# Audio-Board.net
KiCad netlist of a schematic drawn in EAGLE
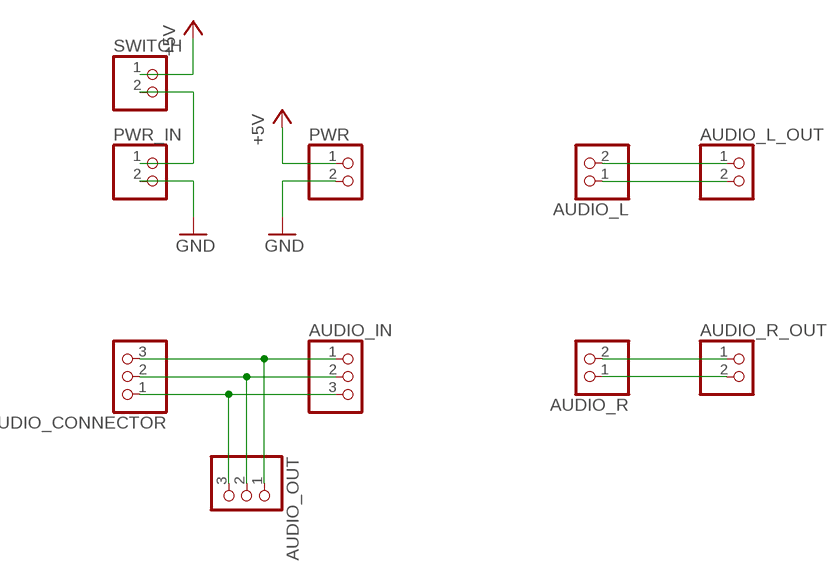
[diagram p0: schematic, sheet 1]

(export (version "E")
  (design (tool "Eeschema 10.0.6"))
  (components
    (comp (ref "AUDIO_CONNECTOR")
      (value "PINHD-1X3")
      (footprint "eagle-import:1X03")
      (libsource (lib "eagle-import") (part "PINHD-1X3"))
    )
    (comp (ref "AUDIO_IN")
      (value "PINHD-1X3")
      (footprint "eagle-import:1X03")
      (libsource (lib "eagle-import") (part "PINHD-1X3"))
    )
    (comp (ref "AUDIO_L")
      (value "PINHD-1X2")
      (footprint "eagle-import:1X02")
      (libsource (lib "eagle-import") (part "PINHD-1X2"))
    )
    (comp (ref "AUDIO_L_OUT")
      (value "PINHD-1X2/90")
      (footprint "eagle-import:1X02_90")
      (libsource (lib "eagle-import") (part "PINHD-1X2/90"))
    )
    (comp (ref "AUDIO_OUT")
      (value "PINHD-1X3")
      (footprint "eagle-import:1X03")
      (libsource (lib "eagle-import") (part "PINHD-1X3"))
    )
    (comp (ref "AUDIO_R")
      (value "PINHD-1X2")
      (footprint "eagle-import:1X02")
      (libsource (lib "eagle-import") (part "PINHD-1X2"))
    )
    (comp (ref "AUDIO_R_OUT")
      (value "PINHD-1X2/90")
      (footprint "eagle-import:1X02_90")
      (libsource (lib "eagle-import") (part "PINHD-1X2/90"))
    )
    (comp (ref "PWR")
      (value "PINHD-1X2")
      (footprint "eagle-import:1X02")
      (libsource (lib "eagle-import") (part "PINHD-1X2"))
    )
    (comp (ref "PWR_IN")
      (value "PINHD-1X2/90")
      (footprint "eagle-import:1X02_90")
      (libsource (lib "eagle-import") (part "PINHD-1X2/90"))
    )
    (comp (ref "SWITCH")
      (value "PINHD-1X2")
      (footprint "eagle-import:1X02")
      (libsource (lib "eagle-import") (part "PINHD-1X2"))
    )
  )
  (nets
    (net (code "1") (name "+5V") (class "Default")
      (node (ref "PWR") (pin "1") (pinfunction "1_1") (pintype "passive"))
      (node (ref "SWITCH") (pin "1") (pinfunction "1_1") (pintype "passive"))
    )
    (net (code "2") (name "GND") (class "Default")
      (node (ref "PWR") (pin "2") (pinfunction "2_2") (pintype "passive"))
      (node (ref "PWR_IN") (pin "2") (pinfunction "2_2") (pintype "passive"))
    )
    (net (code "3") (name "Net-(AUDIO_CONNECTOR-Pad1)") (class "Default")
      (node (ref "AUDIO_CONNECTOR") (pin "1") (pinfunction "1_1") (pintype "passive"))
      (node (ref "AUDIO_IN") (pin "3") (pinfunction "3_3") (pintype "passive"))
      (node (ref "AUDIO_OUT") (pin "3") (pinfunction "3_3") (pintype "passive"))
    )
    (net (code "4") (name "Net-(AUDIO_CONNECTOR-Pad2)") (class "Default")
      (node (ref "AUDIO_CONNECTOR") (pin "2") (pinfunction "2_2") (pintype "passive"))
      (node (ref "AUDIO_IN") (pin "2") (pinfunction "2_2") (pintype "passive"))
      (node (ref "AUDIO_OUT") (pin "2") (pinfunction "2_2") (pintype "passive"))
    )
    (net (code "5") (name "Net-(AUDIO_CONNECTOR-Pad3)") (class "Default")
      (node (ref "AUDIO_CONNECTOR") (pin "3") (pinfunction "3_3") (pintype "passive"))
      (node (ref "AUDIO_IN") (pin "1") (pinfunction "1_1") (pintype "passive"))
      (node (ref "AUDIO_OUT") (pin "1") (pinfunction "1_1") (pintype "passive"))
    )
    (net (code "6") (name "Net-(AUDIO_L-Pad1)") (class "Default")
      (node (ref "AUDIO_L") (pin "1") (pinfunction "1_1") (pintype "passive"))
      (node (ref "AUDIO_L_OUT") (pin "2") (pinfunction "2_2") (pintype "passive"))
    )
    (net (code "7") (name "Net-(AUDIO_L-Pad2)") (class "Default")
      (node (ref "AUDIO_L") (pin "2") (pinfunction "2_2") (pintype "passive"))
      (node (ref "AUDIO_L_OUT") (pin "1") (pinfunction "1_1") (pintype "passive"))
    )
    (net (code "8") (name "Net-(AUDIO_R-Pad1)") (class "Default")
      (node (ref "AUDIO_R") (pin "1") (pinfunction "1_1") (pintype "passive"))
      (node (ref "AUDIO_R_OUT") (pin "2") (pinfunction "2_2") (pintype "passive"))
    )
    (net (code "9") (name "Net-(AUDIO_R-Pad2)") (class "Default")
      (node (ref "AUDIO_R") (pin "2") (pinfunction "2_2") (pintype "passive"))
      (node (ref "AUDIO_R_OUT") (pin "1") (pinfunction "1_1") (pintype "passive"))
    )
    (net (code "10") (name "Net-(PWR_IN-Pad1)") (class "Default")
      (node (ref "PWR_IN") (pin "1") (pinfunction "1_1") (pintype "passive"))
      (node (ref "SWITCH") (pin "2") (pinfunction "2_2") (pintype "passive"))
    )
  )
)
